# MotorShield.net
KiCad netlist of a schematic drawn in EAGLE
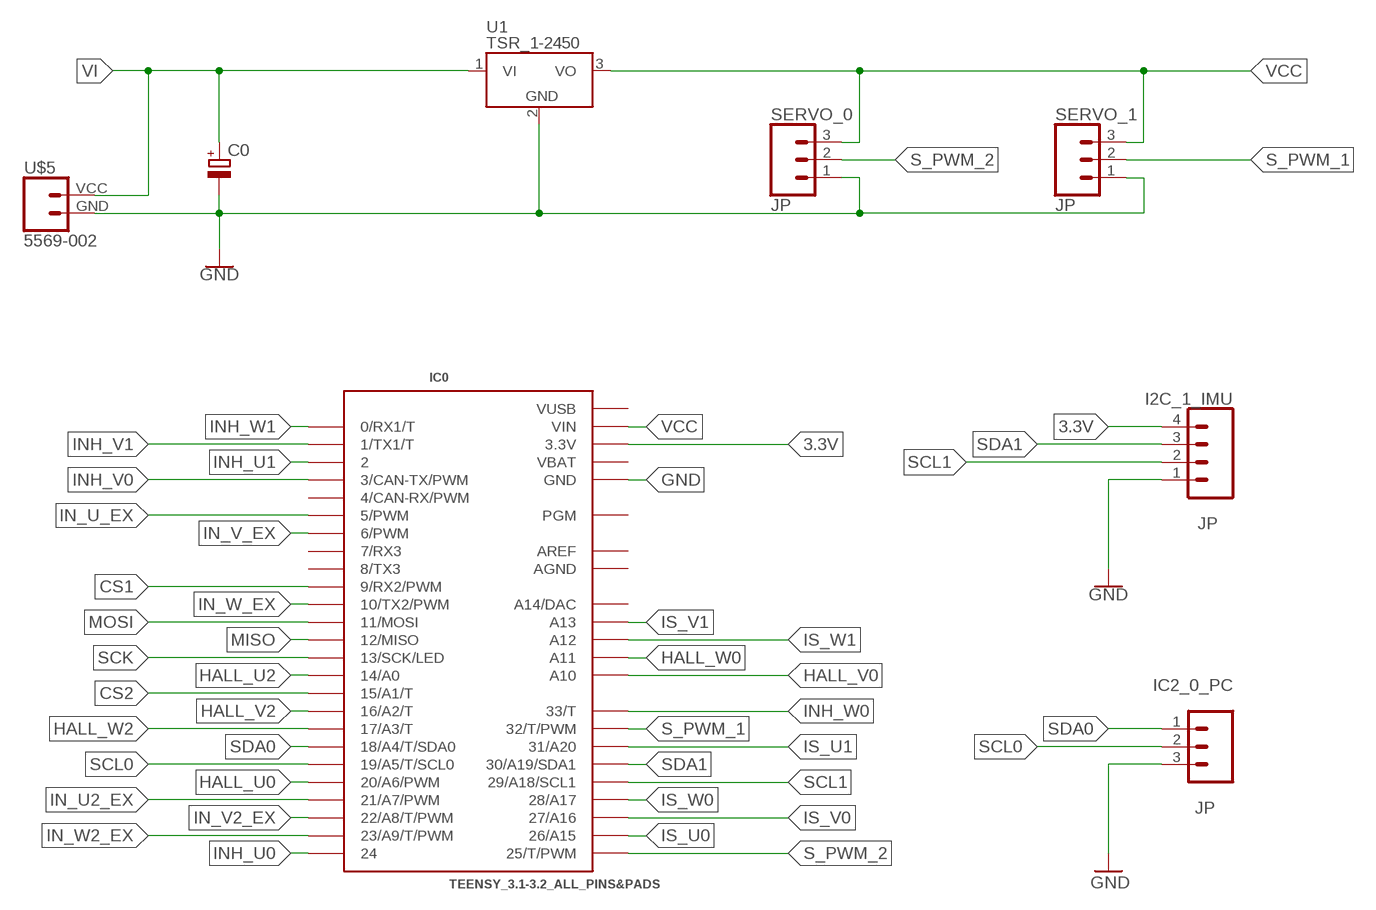
[diagram p0: schematic, sheet 1, part 1 of 2]
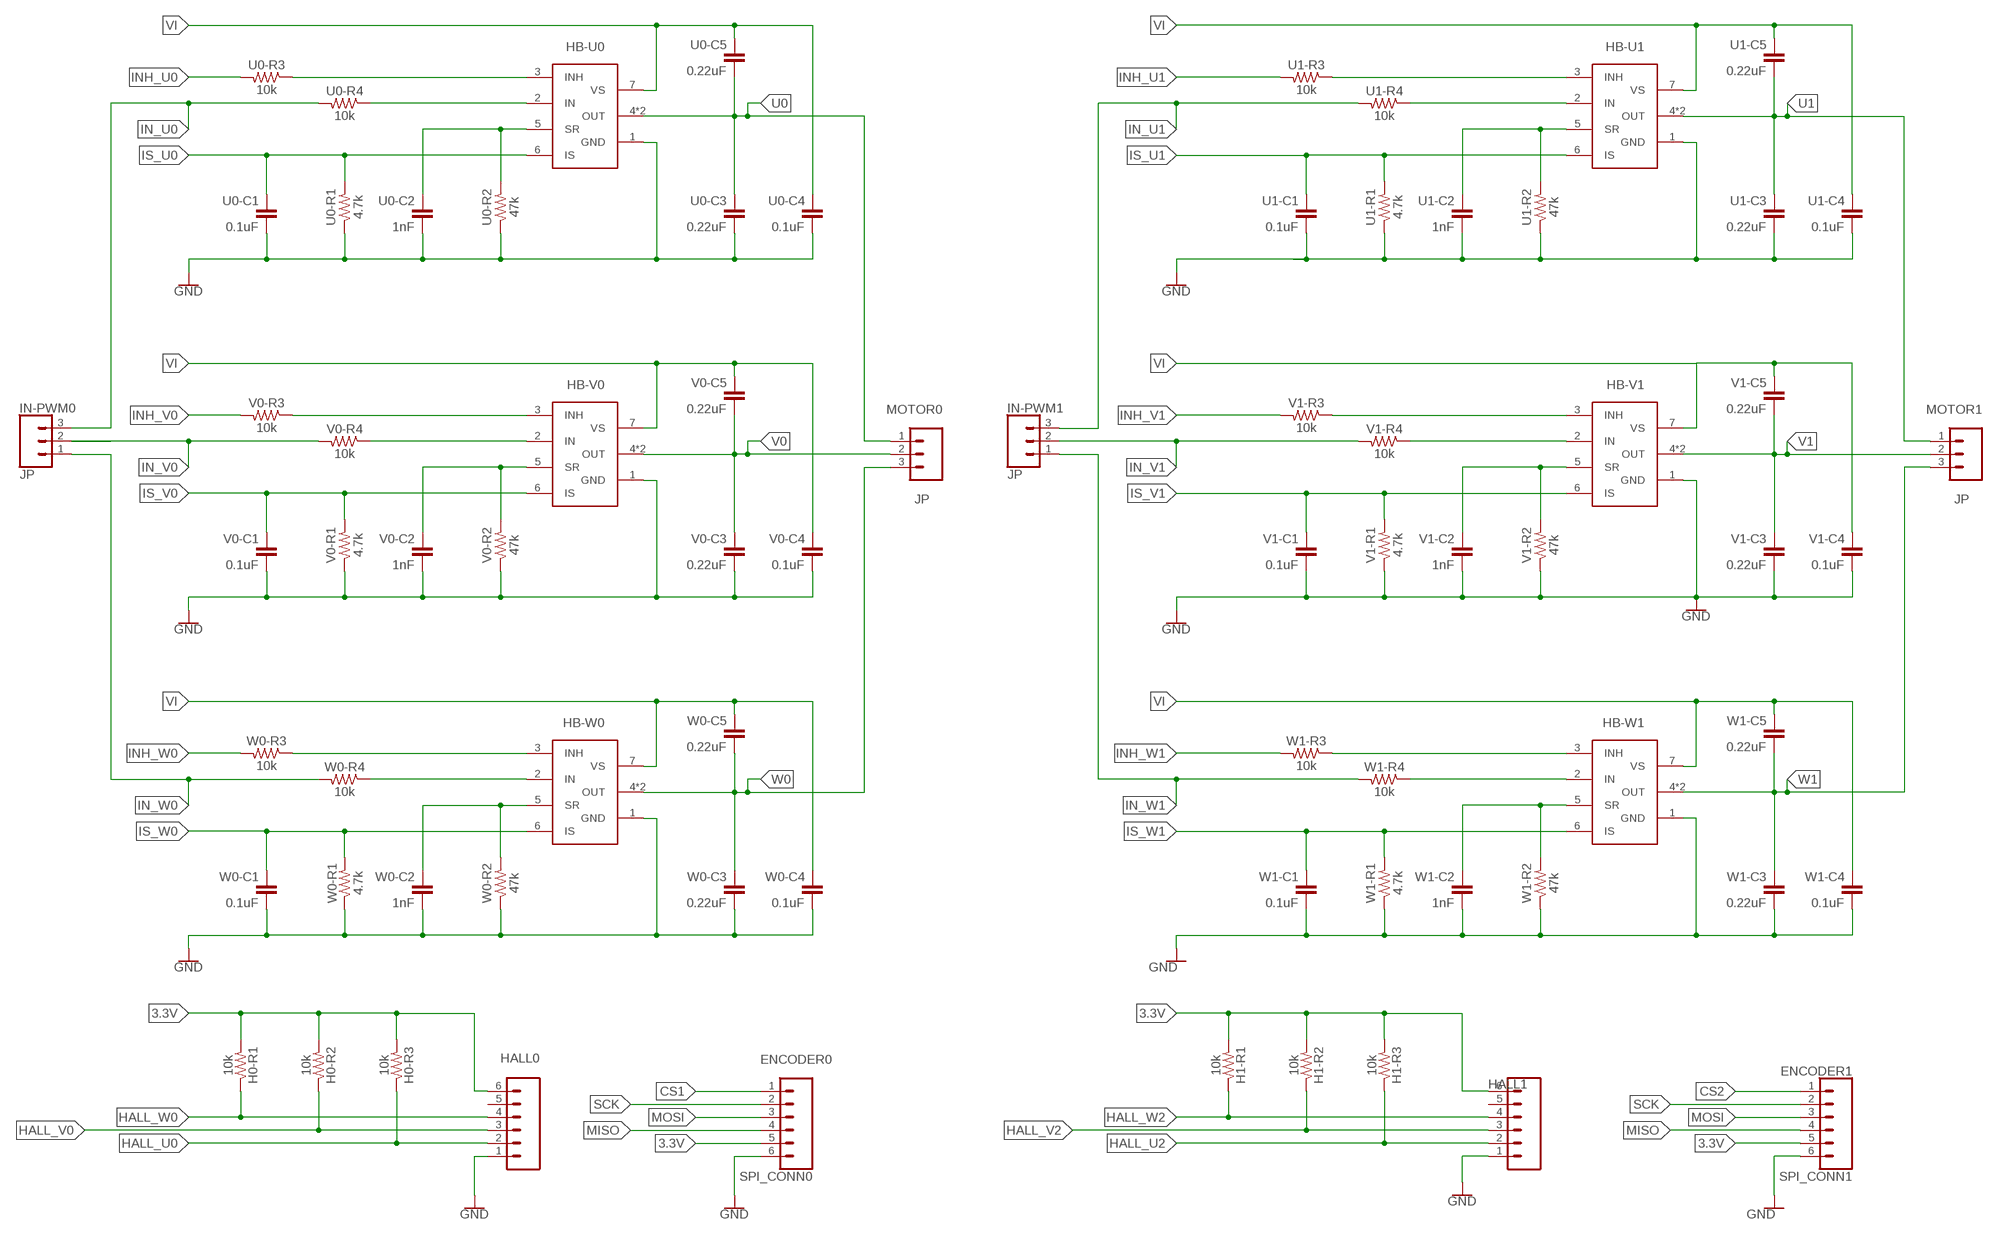
[diagram p1: schematic, sheet 1, part 2 of 2]

(export (version "E")
  (design (tool "Eeschema 10.0.6"))
  (components
    (comp (ref "C0")
      (value "CPOL-EUE2,5-6E")
      (footprint "eagle-import:E2,5-6E")
      (libsource (lib "eagle-import") (part "CPOL-EUE2,5-6E"))
    )
    (comp (ref "H0-R1")
      (value "10k")
      (footprint "eagle-import:0603")
      (libsource (lib "eagle-import") (part "10KOHM-0603-1/10W-1%"))
    )
    (comp (ref "H0-R2")
      (value "10k")
      (footprint "eagle-import:0603")
      (libsource (lib "eagle-import") (part "10KOHM-0603-1/10W-1%"))
    )
    (comp (ref "H0-R3")
      (value "10k")
      (footprint "eagle-import:0603")
      (libsource (lib "eagle-import") (part "10KOHM-0603-1/10W-1%"))
    )
    (comp (ref "H1-R1")
      (value "10k")
      (footprint "eagle-import:0603")
      (libsource (lib "eagle-import") (part "10KOHM-0603-1/10W-1%"))
    )
    (comp (ref "H1-R2")
      (value "10k")
      (footprint "eagle-import:0603")
      (libsource (lib "eagle-import") (part "10KOHM-0603-1/10W-1%"))
    )
    (comp (ref "H1-R3")
      (value "10k")
      (footprint "eagle-import:0603")
      (libsource (lib "eagle-import") (part "10KOHM-0603-1/10W-1%"))
    )
    (comp (ref "HALL0")
      (value "CONN_06SMD-1MM")
      (footprint "eagle-import:1X06-1MM")
      (libsource (lib "eagle-import") (part "CONN_06SMD-1MM"))
    )
    (comp (ref "HALL1")
      (value "CONN_06SMD-1MM")
      (footprint "eagle-import:1X06-1MM")
      (libsource (lib "eagle-import") (part "CONN_06SMD-1MM"))
    )
    (comp (ref "HB-U0")
      (value "IFX007TZZZZ")
      (footprint "eagle-import:P-TO263-7-1")
      (libsource (lib "eagle-import") (part "IFX007TZZZZ"))
    )
    (comp (ref "HB-U1")
      (value "IFX007TZZZZ")
      (footprint "eagle-import:P-TO263-7-1")
      (libsource (lib "eagle-import") (part "IFX007TZZZZ"))
    )
    (comp (ref "HB-V0")
      (value "IFX007TZZZZ")
      (footprint "eagle-import:P-TO263-7-1")
      (libsource (lib "eagle-import") (part "IFX007TZZZZ"))
    )
    (comp (ref "HB-V1")
      (value "IFX007TZZZZ")
      (footprint "eagle-import:P-TO263-7-1")
      (libsource (lib "eagle-import") (part "IFX007TZZZZ"))
    )
    (comp (ref "HB-W0")
      (value "IFX007TZZZZ")
      (footprint "eagle-import:P-TO263-7-1")
      (libsource (lib "eagle-import") (part "IFX007TZZZZ"))
    )
    (comp (ref "HB-W1")
      (value "IFX007TZZZZ")
      (footprint "eagle-import:P-TO263-7-1")
      (libsource (lib "eagle-import") (part "IFX007TZZZZ"))
    )
    (comp (ref "I2C_1_IMU")
      (value "JP")
      (footprint "eagle-import:1X04_NO_SILK")
      (libsource (lib "eagle-import") (part "CONN_041X04_NO_SILK"))
    )
    (comp (ref "IC0")
      (value "TEENSY_3.1-3.2_ALL_PINS&PADS")
      (footprint "eagle-import:TEENSY_3.0-3.2_ALL_PINS_&_PADS")
      (libsource (lib "eagle-import") (part "TEENSY_3.1-3.2_ALL_PINS&PADS"))
    )
    (comp (ref "IC2_0_PC")
      (value "JP")
      (footprint "eagle-import:1X03_NO_SILK")
      (libsource (lib "eagle-import") (part "CONN_031X03_NO_SILK"))
    )
    (comp (ref "IN-PWM0")
      (value "JP")
      (footprint "eagle-import:1X03_NO_SILK")
      (libsource (lib "eagle-import") (part "CONN_031X03_NO_SILK"))
    )
    (comp (ref "IN-PWM1")
      (value "JP")
      (footprint "eagle-import:1X03_NO_SILK")
      (fields (field (name "SPICEPREFIX") "J"))
      (libsource (lib "eagle-import") (part "CONN_031X03_NO_SILK"))
    )
    (comp (ref "MOTOR0")
      (value "JP")
      (footprint "eagle-import:1X03_NO_SILK")
      (libsource (lib "eagle-import") (part "CONN_031X03_NO_SILK"))
    )
    (comp (ref "MOTOR1")
      (value "JP")
      (footprint "eagle-import:1X03_NO_SILK")
      (libsource (lib "eagle-import") (part "CONN_031X03_NO_SILK"))
    )
    (comp (ref "SERVO_0")
      (value "JP")
      (footprint "eagle-import:1X03_NO_SILK")
      (libsource (lib "eagle-import") (part "CONN_031X03_NO_SILK"))
    )
    (comp (ref "SERVO_1")
      (value "JP")
      (footprint "eagle-import:1X03_NO_SILK")
      (libsource (lib "eagle-import") (part "CONN_031X03_NO_SILK"))
    )
    (comp (ref "SPI_CONN0")
      (value "ENCODER0")
      (footprint "eagle-import:1X06-1MM")
      (libsource (lib "eagle-import") (part "CONN_06SMD-1MM"))
    )
    (comp (ref "SPI_CONN1")
      (value "ENCODER1")
      (footprint "eagle-import:1X06-1MM")
      (libsource (lib "eagle-import") (part "CONN_06SMD-1MM"))
    )
    (comp (ref "U$5")
      (value "5569-002")
      (footprint "eagle-import:5569-002")
      (libsource (lib "eagle-import") (part "5569-002"))
    )
    (comp (ref "U0-C1")
      (value "0.1uF")
      (footprint "eagle-import:0603")
      (libsource (lib "eagle-import") (part "0.1UF-0603-25V-5%"))
    )
    (comp (ref "U0-C2")
      (value "1nF")
      (footprint "eagle-import:0603")
      (libsource (lib "eagle-import") (part "1.0NF/1000PF-0603-50V-10%"))
    )
    (comp (ref "U0-C3")
      (value "0.22uF")
      (footprint "eagle-import:0603")
      (libsource (lib "eagle-import") (part "0.22UF-0603-25V-10%"))
    )
    (comp (ref "U0-C4")
      (value "0.1uF")
      (footprint "eagle-import:0603")
      (libsource (lib "eagle-import") (part "0.1UF-0603-25V-5%"))
    )
    (comp (ref "U0-C5")
      (value "0.22uF")
      (footprint "eagle-import:0603")
      (libsource (lib "eagle-import") (part "0.22UF-0603-25V-10%"))
    )
    (comp (ref "U0-R1")
      (value "4.7k")
      (footprint "eagle-import:0603")
      (libsource (lib "eagle-import") (part "4.7KOHM-0603-1/10W-1%"))
    )
    (comp (ref "U0-R2")
      (value "47k")
      (footprint "eagle-import:0603")
      (libsource (lib "eagle-import") (part "47KOHM-0603-1/10W-1%"))
    )
    (comp (ref "U0-R3")
      (value "10k")
      (footprint "eagle-import:0603")
      (libsource (lib "eagle-import") (part "10KOHM-0603-1/10W-1%"))
    )
    (comp (ref "U0-R4")
      (value "10k")
      (footprint "eagle-import:0603")
      (libsource (lib "eagle-import") (part "10KOHM-0603-1/10W-1%"))
    )
    (comp (ref "U1")
      (value "TSR_1-2450")
      (footprint "eagle-import:TSR-1")
      (libsource (lib "eagle-import") (part "TSR_1-2450"))
    )
    (comp (ref "U1-C1")
      (value "0.1uF")
      (footprint "eagle-import:0603")
      (libsource (lib "eagle-import") (part "0.1UF-0603-25V-5%"))
    )
    (comp (ref "U1-C2")
      (value "1nF")
      (footprint "eagle-import:0603")
      (libsource (lib "eagle-import") (part "1.0NF/1000PF-0603-50V-10%"))
    )
    (comp (ref "U1-C3")
      (value "0.22uF")
      (footprint "eagle-import:0603")
      (libsource (lib "eagle-import") (part "0.22UF-0603-25V-10%"))
    )
    (comp (ref "U1-C4")
      (value "0.1uF")
      (footprint "eagle-import:0603")
      (libsource (lib "eagle-import") (part "0.1UF-0603-25V-5%"))
    )
    (comp (ref "U1-C5")
      (value "0.22uF")
      (footprint "eagle-import:0603")
      (libsource (lib "eagle-import") (part "0.22UF-0603-25V-10%"))
    )
    (comp (ref "U1-R1")
      (value "4.7k")
      (footprint "eagle-import:0603")
      (libsource (lib "eagle-import") (part "4.7KOHM-0603-1/10W-1%"))
    )
    (comp (ref "U1-R2")
      (value "47k")
      (footprint "eagle-import:0603")
      (libsource (lib "eagle-import") (part "47KOHM-0603-1/10W-1%"))
    )
    (comp (ref "U1-R3")
      (value "10k")
      (footprint "eagle-import:0603")
      (libsource (lib "eagle-import") (part "10KOHM-0603-1/10W-1%"))
    )
    (comp (ref "U1-R4")
      (value "10k")
      (footprint "eagle-import:0603")
      (libsource (lib "eagle-import") (part "10KOHM-0603-1/10W-1%"))
    )
    (comp (ref "V0-C1")
      (value "0.1uF")
      (footprint "eagle-import:0603")
      (libsource (lib "eagle-import") (part "0.1UF-0603-25V-5%"))
    )
    (comp (ref "V0-C2")
      (value "1nF")
      (footprint "eagle-import:0603")
      (libsource (lib "eagle-import") (part "1.0NF/1000PF-0603-50V-10%"))
    )
    (comp (ref "V0-C3")
      (value "0.22uF")
      (footprint "eagle-import:0603")
      (libsource (lib "eagle-import") (part "0.22UF-0603-25V-10%"))
    )
    (comp (ref "V0-C4")
      (value "0.1uF")
      (footprint "eagle-import:0603")
      (libsource (lib "eagle-import") (part "0.1UF-0603-25V-5%"))
    )
    (comp (ref "V0-C5")
      (value "0.22uF")
      (footprint "eagle-import:0603")
      (libsource (lib "eagle-import") (part "0.22UF-0603-25V-10%"))
    )
    (comp (ref "V0-R1")
      (value "4.7k")
      (footprint "eagle-import:0603")
      (libsource (lib "eagle-import") (part "4.7KOHM-0603-1/10W-1%"))
    )
    (comp (ref "V0-R2")
      (value "47k")
      (footprint "eagle-import:0603")
      (libsource (lib "eagle-import") (part "47KOHM-0603-1/10W-1%"))
    )
    (comp (ref "V0-R3")
      (value "10k")
      (footprint "eagle-import:0603")
      (libsource (lib "eagle-import") (part "10KOHM-0603-1/10W-1%"))
    )
    (comp (ref "V0-R4")
      (value "10k")
      (footprint "eagle-import:0603")
      (libsource (lib "eagle-import") (part "10KOHM-0603-1/10W-1%"))
    )
    (comp (ref "V1-C1")
      (value "0.1uF")
      (footprint "eagle-import:0603")
      (libsource (lib "eagle-import") (part "0.1UF-0603-25V-5%"))
    )
    (comp (ref "V1-C2")
      (value "1nF")
      (footprint "eagle-import:0603")
      (libsource (lib "eagle-import") (part "1.0NF/1000PF-0603-50V-10%"))
    )
    (comp (ref "V1-C3")
      (value "0.22uF")
      (footprint "eagle-import:0603")
      (libsource (lib "eagle-import") (part "0.22UF-0603-25V-10%"))
    )
    (comp (ref "V1-C4")
      (value "0.1uF")
      (footprint "eagle-import:0603")
      (libsource (lib "eagle-import") (part "0.1UF-0603-25V-5%"))
    )
    (comp (ref "V1-C5")
      (value "0.22uF")
      (footprint "eagle-import:0603")
      (libsource (lib "eagle-import") (part "0.22UF-0603-25V-10%"))
    )
    (comp (ref "V1-R1")
      (value "4.7k")
      (footprint "eagle-import:0603")
      (libsource (lib "eagle-import") (part "4.7KOHM-0603-1/10W-1%"))
    )
    (comp (ref "V1-R2")
      (value "47k")
      (footprint "eagle-import:0603")
      (libsource (lib "eagle-import") (part "47KOHM-0603-1/10W-1%"))
    )
    (comp (ref "V1-R3")
      (value "10k")
      (footprint "eagle-import:0603")
      (libsource (lib "eagle-import") (part "10KOHM-0603-1/10W-1%"))
    )
    (comp (ref "V1-R4")
      (value "10k")
      (footprint "eagle-import:0603")
      (libsource (lib "eagle-import") (part "10KOHM-0603-1/10W-1%"))
    )
    (comp (ref "W0-C1")
      (value "0.1uF")
      (footprint "eagle-import:0603")
      (libsource (lib "eagle-import") (part "0.1UF-0603-25V-5%"))
    )
    (comp (ref "W0-C2")
      (value "1nF")
      (footprint "eagle-import:0603")
      (libsource (lib "eagle-import") (part "1.0NF/1000PF-0603-50V-10%"))
    )
    (comp (ref "W0-C3")
      (value "0.22uF")
      (footprint "eagle-import:0603")
      (libsource (lib "eagle-import") (part "0.22UF-0603-25V-10%"))
    )
    (comp (ref "W0-C4")
      (value "0.1uF")
      (footprint "eagle-import:0603")
      (libsource (lib "eagle-import") (part "0.1UF-0603-25V-5%"))
    )
    (comp (ref "W0-C5")
      (value "0.22uF")
      (footprint "eagle-import:0603")
      (libsource (lib "eagle-import") (part "0.22UF-0603-25V-10%"))
    )
    (comp (ref "W0-R1")
      (value "4.7k")
      (footprint "eagle-import:0603")
      (libsource (lib "eagle-import") (part "4.7KOHM-0603-1/10W-1%"))
    )
    (comp (ref "W0-R2")
      (value "47k")
      (footprint "eagle-import:0603")
      (libsource (lib "eagle-import") (part "47KOHM-0603-1/10W-1%"))
    )
    (comp (ref "W0-R3")
      (value "10k")
      (footprint "eagle-import:0603")
      (libsource (lib "eagle-import") (part "10KOHM-0603-1/10W-1%"))
    )
    (comp (ref "W0-R4")
      (value "10k")
      (footprint "eagle-import:0603")
      (libsource (lib "eagle-import") (part "10KOHM-0603-1/10W-1%"))
    )
    (comp (ref "W1-C1")
      (value "0.1uF")
      (footprint "eagle-import:0603")
      (libsource (lib "eagle-import") (part "0.1UF-0603-25V-5%"))
    )
    (comp (ref "W1-C2")
      (value "1nF")
      (footprint "eagle-import:0603")
      (libsource (lib "eagle-import") (part "1.0NF/1000PF-0603-50V-10%"))
    )
    (comp (ref "W1-C3")
      (value "0.22uF")
      (footprint "eagle-import:0603")
      (libsource (lib "eagle-import") (part "0.22UF-0603-25V-10%"))
    )
    (comp (ref "W1-C4")
      (value "0.1uF")
      (footprint "eagle-import:0603")
      (libsource (lib "eagle-import") (part "0.1UF-0603-25V-5%"))
    )
    (comp (ref "W1-C5")
      (value "0.22uF")
      (footprint "eagle-import:0603")
      (libsource (lib "eagle-import") (part "0.22UF-0603-25V-10%"))
    )
    (comp (ref "W1-R1")
      (value "4.7k")
      (footprint "eagle-import:0603")
      (libsource (lib "eagle-import") (part "4.7KOHM-0603-1/10W-1%"))
    )
    (comp (ref "W1-R2")
      (value "47k")
      (footprint "eagle-import:0603")
      (libsource (lib "eagle-import") (part "47KOHM-0603-1/10W-1%"))
    )
    (comp (ref "W1-R3")
      (value "10k")
      (footprint "eagle-import:0603")
      (libsource (lib "eagle-import") (part "10KOHM-0603-1/10W-1%"))
    )
    (comp (ref "W1-R4")
      (value "10k")
      (footprint "eagle-import:0603")
      (libsource (lib "eagle-import") (part "10KOHM-0603-1/10W-1%"))
    )
  )
  (nets
    (net (code "1") (name "/AGND") (class "Default")
      (node (ref "IC0") (pin "AGND") (pinfunction "AGND_AGND") (pintype "power_in"))
    )
    (net (code "2") (name "/AREF") (class "Default")
      (node (ref "IC0") (pin "AREF") (pinfunction "AREF_AREF") (pintype "power_in"))
    )
    (net (code "3") (name "/VBAT") (class "Default")
      (node (ref "IC0") (pin "VBAT") (pinfunction "VBAT_VBAT") (pintype "power_in"))
    )
    (net (code "4") (name "/VUSB") (class "Default")
      (node (ref "IC0") (pin "VUSB") (pinfunction "VUSB_VUSB") (pintype "power_in"))
    )
    (net (code "5") (name "3.3V") (class "Default")
      (node (ref "H0-R1") (pin "2") (pinfunction "2_2") (pintype "passive"))
      (node (ref "H0-R2") (pin "2") (pinfunction "2_2") (pintype "passive"))
      (node (ref "H0-R3") (pin "2") (pinfunction "2_2") (pintype "passive"))
      (node (ref "H1-R1") (pin "2") (pinfunction "2_2") (pintype "passive"))
      (node (ref "H1-R2") (pin "2") (pinfunction "2_2") (pintype "passive"))
      (node (ref "H1-R3") (pin "2") (pinfunction "2_2") (pintype "passive"))
      (node (ref "HALL0") (pin "6") (pinfunction "6_6") (pintype "passive"))
      (node (ref "HALL1") (pin "6") (pinfunction "6_6") (pintype "passive"))
      (node (ref "I2C_1_IMU") (pin "4") (pinfunction "4_4") (pintype "passive"))
      (node (ref "IC0") (pin "3.3V") (pinfunction "3.3V_3.3V") (pintype "power_in"))
      (node (ref "IC0") (pin "3.3V1") (pinfunction "3.3V_3.3V1") (pintype "power_in"))
      (node (ref "IC0") (pin "3.3V2") (pinfunction "3.3V_3.3V2") (pintype "power_in"))
      (node (ref "SPI_CONN0") (pin "5") (pinfunction "5_5") (pintype "passive"))
      (node (ref "SPI_CONN1") (pin "5") (pinfunction "5_5") (pintype "passive"))
    )
    (net (code "6") (name "CS1") (class "Default")
      (node (ref "IC0") (pin "9") (pinfunction "9/RX2/PWM_9") (pintype "bidirectional"))
      (node (ref "SPI_CONN0") (pin "1") (pinfunction "1_1") (pintype "passive"))
    )
    (net (code "7") (name "CS2") (class "Default")
      (node (ref "IC0") (pin "15/A1") (pinfunction "15/A1/T_15/A1") (pintype "bidirectional"))
      (node (ref "SPI_CONN1") (pin "1") (pinfunction "1_1") (pintype "passive"))
    )
    (net (code "8") (name "GND") (class "Default")
      (node (ref "C0") (pin "-") (pinfunction "-_-") (pintype "passive"))
      (node (ref "HALL0") (pin "1") (pinfunction "1_1") (pintype "passive"))
      (node (ref "HALL1") (pin "1") (pinfunction "1_1") (pintype "passive"))
      (node (ref "HB-U0") (pin "1") (pinfunction "GND_1") (pintype "power_in"))
      (node (ref "HB-U1") (pin "1") (pinfunction "GND_1") (pintype "power_in"))
      (node (ref "HB-V0") (pin "1") (pinfunction "GND_1") (pintype "power_in"))
      (node (ref "HB-V1") (pin "1") (pinfunction "GND_1") (pintype "power_in"))
      (node (ref "HB-W0") (pin "1") (pinfunction "GND_1") (pintype "power_in"))
      (node (ref "HB-W1") (pin "1") (pinfunction "GND_1") (pintype "power_in"))
      (node (ref "I2C_1_IMU") (pin "1") (pinfunction "1_1") (pintype "passive"))
      (node (ref "IC0") (pin "GND") (pinfunction "GND_GND") (pintype "power_in"))
      (node (ref "IC0") (pin "GND1") (pinfunction "GND_GND1") (pintype "power_in"))
      (node (ref "IC0") (pin "GND2") (pinfunction "GND_GND2") (pintype "power_in"))
      (node (ref "IC2_0_PC") (pin "3") (pinfunction "3_3") (pintype "passive"))
      (node (ref "SERVO_0") (pin "1") (pinfunction "1_1") (pintype "passive"))
      (node (ref "SERVO_1") (pin "1") (pinfunction "1_1") (pintype "passive"))
      (node (ref "SPI_CONN0") (pin "6") (pinfunction "6_6") (pintype "passive"))
      (node (ref "SPI_CONN1") (pin "6") (pinfunction "6_6") (pintype "passive"))
      (node (ref "U$5") (pin "GND") (pinfunction "1_GND") (pintype "passive"))
      (node (ref "U0-C1") (pin "2") (pinfunction "2_2") (pintype "passive"))
      (node (ref "U0-C2") (pin "1") (pinfunction "1_1") (pintype "passive"))
      (node (ref "U0-C3") (pin "1") (pinfunction "1_1") (pintype "passive"))
      (node (ref "U0-C4") (pin "2") (pinfunction "2_2") (pintype "passive"))
      (node (ref "U0-R1") (pin "1") (pinfunction "1_1") (pintype "passive"))
      (node (ref "U0-R2") (pin "1") (pinfunction "1_1") (pintype "passive"))
      (node (ref "U1") (pin "2") (pinfunction "GND_2") (pintype "power_in"))
      (node (ref "U1-C1") (pin "2") (pinfunction "2_2") (pintype "passive"))
      (node (ref "U1-C2") (pin "1") (pinfunction "1_1") (pintype "passive"))
      (node (ref "U1-C3") (pin "1") (pinfunction "1_1") (pintype "passive"))
      (node (ref "U1-C4") (pin "2") (pinfunction "2_2") (pintype "passive"))
      (node (ref "U1-R1") (pin "1") (pinfunction "1_1") (pintype "passive"))
      (node (ref "U1-R2") (pin "1") (pinfunction "1_1") (pintype "passive"))
      (node (ref "V0-C1") (pin "2") (pinfunction "2_2") (pintype "passive"))
      (node (ref "V0-C2") (pin "1") (pinfunction "1_1") (pintype "passive"))
      (node (ref "V0-C3") (pin "1") (pinfunction "1_1") (pintype "passive"))
      (node (ref "V0-C4") (pin "2") (pinfunction "2_2") (pintype "passive"))
      (node (ref "V0-R1") (pin "1") (pinfunction "1_1") (pintype "passive"))
      (node (ref "V0-R2") (pin "1") (pinfunction "1_1") (pintype "passive"))
      (node (ref "V1-C1") (pin "2") (pinfunction "2_2") (pintype "passive"))
      (node (ref "V1-C2") (pin "1") (pinfunction "1_1") (pintype "passive"))
      (node (ref "V1-C3") (pin "1") (pinfunction "1_1") (pintype "passive"))
      (node (ref "V1-C4") (pin "2") (pinfunction "2_2") (pintype "passive"))
      (node (ref "V1-R1") (pin "1") (pinfunction "1_1") (pintype "passive"))
      (node (ref "V1-R2") (pin "1") (pinfunction "1_1") (pintype "passive"))
      (node (ref "W0-C1") (pin "2") (pinfunction "2_2") (pintype "passive"))
      (node (ref "W0-C2") (pin "1") (pinfunction "1_1") (pintype "passive"))
      (node (ref "W0-C3") (pin "1") (pinfunction "1_1") (pintype "passive"))
      (node (ref "W0-C4") (pin "2") (pinfunction "2_2") (pintype "passive"))
      (node (ref "W0-R1") (pin "1") (pinfunction "1_1") (pintype "passive"))
      (node (ref "W0-R2") (pin "1") (pinfunction "1_1") (pintype "passive"))
      (node (ref "W1-C1") (pin "2") (pinfunction "2_2") (pintype "passive"))
      (node (ref "W1-C2") (pin "1") (pinfunction "1_1") (pintype "passive"))
      (node (ref "W1-C3") (pin "1") (pinfunction "1_1") (pintype "passive"))
      (node (ref "W1-C4") (pin "2") (pinfunction "2_2") (pintype "passive"))
      (node (ref "W1-R1") (pin "1") (pinfunction "1_1") (pintype "passive"))
      (node (ref "W1-R2") (pin "1") (pinfunction "1_1") (pintype "passive"))
    )
    (net (code "9") (name "HALL_U0") (class "Default")
      (node (ref "H0-R3") (pin "1") (pinfunction "1_1") (pintype "passive"))
      (node (ref "HALL0") (pin "2") (pinfunction "2_2") (pintype "passive"))
      (node (ref "IC0") (pin "20/A6") (pinfunction "20/A6/PWM_20/A6") (pintype "bidirectional"))
    )
    (net (code "10") (name "HALL_U2") (class "Default")
      (node (ref "H1-R3") (pin "1") (pinfunction "1_1") (pintype "passive"))
      (node (ref "HALL1") (pin "2") (pinfunction "2_2") (pintype "passive"))
      (node (ref "IC0") (pin "14/A0") (pinfunction "14/A0_14/A0") (pintype "bidirectional"))
    )
    (net (code "11") (name "HALL_V0") (class "Default")
      (node (ref "H0-R2") (pin "1") (pinfunction "1_1") (pintype "passive"))
      (node (ref "HALL0") (pin "3") (pinfunction "3_3") (pintype "passive"))
      (node (ref "IC0") (pin "A10") (pinfunction "A10_A10") (pintype "bidirectional"))
    )
    (net (code "12") (name "HALL_V2") (class "Default")
      (node (ref "H1-R2") (pin "1") (pinfunction "1_1") (pintype "passive"))
      (node (ref "HALL1") (pin "3") (pinfunction "3_3") (pintype "passive"))
      (node (ref "IC0") (pin "16/A2") (pinfunction "16/A2/T_16/A2") (pintype "bidirectional"))
    )
    (net (code "13") (name "HALL_W0") (class "Default")
      (node (ref "H0-R1") (pin "1") (pinfunction "1_1") (pintype "passive"))
      (node (ref "HALL0") (pin "4") (pinfunction "4_4") (pintype "passive"))
      (node (ref "IC0") (pin "A11") (pinfunction "A11_A11") (pintype "bidirectional"))
    )
    (net (code "14") (name "HALL_W2") (class "Default")
      (node (ref "H1-R1") (pin "1") (pinfunction "1_1") (pintype "passive"))
      (node (ref "HALL1") (pin "4") (pinfunction "4_4") (pintype "passive"))
      (node (ref "IC0") (pin "17/A3") (pinfunction "17/A3/T_17/A3") (pintype "bidirectional"))
    )
    (net (code "15") (name "INH_U0") (class "Default")
      (node (ref "IC0") (pin "24") (pinfunction "24_24") (pintype "bidirectional"))
      (node (ref "U0-R3") (pin "2") (pinfunction "2_2") (pintype "passive"))
    )
    (net (code "16") (name "INH_U1") (class "Default")
      (node (ref "IC0") (pin "2") (pinfunction "2_2") (pintype "bidirectional"))
      (node (ref "U1-R3") (pin "2") (pinfunction "2_2") (pintype "passive"))
    )
    (net (code "17") (name "INH_V0") (class "Default")
      (node (ref "IC0") (pin "3") (pinfunction "3/CAN-TX/PWM_3") (pintype "bidirectional"))
      (node (ref "V0-R3") (pin "2") (pinfunction "2_2") (pintype "passive"))
    )
    (net (code "18") (name "INH_V1") (class "Default")
      (node (ref "IC0") (pin "1") (pinfunction "1/TX1/T_1") (pintype "bidirectional"))
      (node (ref "V1-R3") (pin "2") (pinfunction "2_2") (pintype "passive"))
    )
    (net (code "19") (name "INH_W0") (class "Default")
      (node (ref "IC0") (pin "33") (pinfunction "33/T_33") (pintype "bidirectional"))
      (node (ref "W0-R3") (pin "2") (pinfunction "2_2") (pintype "passive"))
    )
    (net (code "20") (name "INH_W1") (class "Default")
      (node (ref "IC0") (pin "0") (pinfunction "0/RX1/T_0") (pintype "bidirectional"))
      (node (ref "W1-R3") (pin "2") (pinfunction "2_2") (pintype "passive"))
    )
    (net (code "21") (name "IN_U0") (class "Default")
      (node (ref "IN-PWM0") (pin "3") (pinfunction "3_3") (pintype "passive"))
      (node (ref "U0-R4") (pin "2") (pinfunction "2_2") (pintype "passive"))
    )
    (net (code "22") (name "IN_U1") (class "Default")
      (node (ref "IN-PWM1") (pin "3") (pinfunction "3_3") (pintype "passive"))
      (node (ref "U1-R4") (pin "2") (pinfunction "2_2") (pintype "passive"))
    )
    (net (code "23") (name "IN_U2_EX") (class "Default")
      (node (ref "IC0") (pin "21/A7") (pinfunction "21/A7/PWM_21/A7") (pintype "bidirectional"))
    )
    (net (code "24") (name "IN_U_EX") (class "Default")
      (node (ref "IC0") (pin "5") (pinfunction "5/PWM_5") (pintype "bidirectional"))
    )
    (net (code "25") (name "IN_V0") (class "Default")
      (node (ref "IN-PWM0") (pin "2") (pinfunction "2_2") (pintype "passive"))
      (node (ref "V0-R4") (pin "2") (pinfunction "2_2") (pintype "passive"))
    )
    (net (code "26") (name "IN_V1") (class "Default")
      (node (ref "IN-PWM1") (pin "2") (pinfunction "2_2") (pintype "passive"))
      (node (ref "V1-R4") (pin "2") (pinfunction "2_2") (pintype "passive"))
    )
    (net (code "27") (name "IN_V2_EX") (class "Default")
      (node (ref "IC0") (pin "22/A8") (pinfunction "22/A8/T/PWM_22/A8") (pintype "bidirectional"))
    )
    (net (code "28") (name "IN_V_EX") (class "Default")
      (node (ref "IC0") (pin "6") (pinfunction "6/PWM_6") (pintype "bidirectional"))
    )
    (net (code "29") (name "IN_W0") (class "Default")
      (node (ref "IN-PWM0") (pin "1") (pinfunction "1_1") (pintype "passive"))
      (node (ref "W0-R4") (pin "2") (pinfunction "2_2") (pintype "passive"))
    )
    (net (code "30") (name "IN_W1") (class "Default")
      (node (ref "IN-PWM1") (pin "1") (pinfunction "1_1") (pintype "passive"))
      (node (ref "W1-R4") (pin "2") (pinfunction "2_2") (pintype "passive"))
    )
    (net (code "31") (name "IN_W2_EX") (class "Default")
      (node (ref "IC0") (pin "23/A9") (pinfunction "23/A9/T/PWM_23/A9") (pintype "bidirectional"))
    )
    (net (code "32") (name "IN_W_EX") (class "Default")
      (node (ref "IC0") (pin "10") (pinfunction "10/TX2/PWM_10") (pintype "bidirectional"))
    )
    (net (code "33") (name "IS_U0") (class "Default")
      (node (ref "HB-U0") (pin "6") (pinfunction "IS_6") (pintype "output"))
      (node (ref "IC0") (pin "26") (pinfunction "26/A15_26") (pintype "bidirectional"))
      (node (ref "U0-C1") (pin "1") (pinfunction "1_1") (pintype "passive"))
      (node (ref "U0-R1") (pin "2") (pinfunction "2_2") (pintype "passive"))
    )
    (net (code "34") (name "IS_U1") (class "Default")
      (node (ref "HB-U1") (pin "6") (pinfunction "IS_6") (pintype "output"))
      (node (ref "IC0") (pin "31") (pinfunction "31/A20_31") (pintype "bidirectional"))
      (node (ref "U1-C1") (pin "1") (pinfunction "1_1") (pintype "passive"))
      (node (ref "U1-R1") (pin "2") (pinfunction "2_2") (pintype "passive"))
    )
    (net (code "35") (name "IS_V0") (class "Default")
      (node (ref "HB-V0") (pin "6") (pinfunction "IS_6") (pintype "output"))
      (node (ref "IC0") (pin "27") (pinfunction "27/A16_27") (pintype "bidirectional"))
      (node (ref "V0-C1") (pin "1") (pinfunction "1_1") (pintype "passive"))
      (node (ref "V0-R1") (pin "2") (pinfunction "2_2") (pintype "passive"))
    )
    (net (code "36") (name "IS_V1") (class "Default")
      (node (ref "HB-V1") (pin "6") (pinfunction "IS_6") (pintype "output"))
      (node (ref "IC0") (pin "A13") (pinfunction "A13_A13") (pintype "bidirectional"))
      (node (ref "V1-C1") (pin "1") (pinfunction "1_1") (pintype "passive"))
      (node (ref "V1-R1") (pin "2") (pinfunction "2_2") (pintype "passive"))
    )
    (net (code "37") (name "IS_W0") (class "Default")
      (node (ref "HB-W0") (pin "6") (pinfunction "IS_6") (pintype "output"))
      (node (ref "IC0") (pin "28") (pinfunction "28/A17_28") (pintype "bidirectional"))
      (node (ref "W0-C1") (pin "1") (pinfunction "1_1") (pintype "passive"))
      (node (ref "W0-R1") (pin "2") (pinfunction "2_2") (pintype "passive"))
    )
    (net (code "38") (name "IS_W1") (class "Default")
      (node (ref "HB-W1") (pin "6") (pinfunction "IS_6") (pintype "output"))
      (node (ref "IC0") (pin "A12") (pinfunction "A12_A12") (pintype "bidirectional"))
      (node (ref "W1-C1") (pin "1") (pinfunction "1_1") (pintype "passive"))
      (node (ref "W1-R1") (pin "2") (pinfunction "2_2") (pintype "passive"))
    )
    (net (code "39") (name "MISO") (class "Default")
      (node (ref "IC0") (pin "12") (pinfunction "12/MISO_12") (pintype "bidirectional"))
      (node (ref "SPI_CONN0") (pin "4") (pinfunction "4_4") (pintype "passive"))
      (node (ref "SPI_CONN1") (pin "4") (pinfunction "4_4") (pintype "passive"))
    )
    (net (code "40") (name "MOSI") (class "Default")
      (node (ref "IC0") (pin "11") (pinfunction "11/MOSI_11") (pintype "bidirectional"))
      (node (ref "SPI_CONN0") (pin "3") (pinfunction "3_3") (pintype "passive"))
      (node (ref "SPI_CONN1") (pin "3") (pinfunction "3_3") (pintype "passive"))
    )
    (net (code "41") (name "Net-(HB-U0-IN)") (class "Default")
      (node (ref "HB-U0") (pin "2") (pinfunction "IN_2") (pintype "input"))
      (node (ref "U0-R4") (pin "1") (pinfunction "1_1") (pintype "passive"))
    )
    (net (code "42") (name "Net-(HB-U0-INH)") (class "Default")
      (node (ref "HB-U0") (pin "3") (pinfunction "INH_3") (pintype "bidirectional"))
      (node (ref "U0-R3") (pin "1") (pinfunction "1_1") (pintype "passive"))
    )
    (net (code "43") (name "Net-(HB-U0-SR)") (class "Default")
      (node (ref "HB-U0") (pin "5") (pinfunction "SR_5") (pintype "input"))
      (node (ref "U0-C2") (pin "2") (pinfunction "2_2") (pintype "passive"))
      (node (ref "U0-R2") (pin "2") (pinfunction "2_2") (pintype "passive"))
    )
    (net (code "44") (name "Net-(HB-U1-IN)") (class "Default")
      (node (ref "HB-U1") (pin "2") (pinfunction "IN_2") (pintype "input"))
      (node (ref "U1-R4") (pin "1") (pinfunction "1_1") (pintype "passive"))
    )
    (net (code "45") (name "Net-(HB-U1-INH)") (class "Default")
      (node (ref "HB-U1") (pin "3") (pinfunction "INH_3") (pintype "bidirectional"))
      (node (ref "U1-R3") (pin "1") (pinfunction "1_1") (pintype "passive"))
    )
    (net (code "46") (name "Net-(HB-U1-SR)") (class "Default")
      (node (ref "HB-U1") (pin "5") (pinfunction "SR_5") (pintype "input"))
      (node (ref "U1-C2") (pin "2") (pinfunction "2_2") (pintype "passive"))
      (node (ref "U1-R2") (pin "2") (pinfunction "2_2") (pintype "passive"))
    )
    (net (code "47") (name "Net-(HB-V0-IN)") (class "Default")
      (node (ref "HB-V0") (pin "2") (pinfunction "IN_2") (pintype "input"))
      (node (ref "V0-R4") (pin "1") (pinfunction "1_1") (pintype "passive"))
    )
    (net (code "48") (name "Net-(HB-V0-INH)") (class "Default")
      (node (ref "HB-V0") (pin "3") (pinfunction "INH_3") (pintype "bidirectional"))
      (node (ref "V0-R3") (pin "1") (pinfunction "1_1") (pintype "passive"))
    )
    (net (code "49") (name "Net-(HB-V0-SR)") (class "Default")
      (node (ref "HB-V0") (pin "5") (pinfunction "SR_5") (pintype "input"))
      (node (ref "V0-C2") (pin "2") (pinfunction "2_2") (pintype "passive"))
      (node (ref "V0-R2") (pin "2") (pinfunction "2_2") (pintype "passive"))
    )
    (net (code "50") (name "Net-(HB-V1-IN)") (class "Default")
      (node (ref "HB-V1") (pin "2") (pinfunction "IN_2") (pintype "input"))
      (node (ref "V1-R4") (pin "1") (pinfunction "1_1") (pintype "passive"))
    )
    (net (code "51") (name "Net-(HB-V1-INH)") (class "Default")
      (node (ref "HB-V1") (pin "3") (pinfunction "INH_3") (pintype "bidirectional"))
      (node (ref "V1-R3") (pin "1") (pinfunction "1_1") (pintype "passive"))
    )
    (net (code "52") (name "Net-(HB-V1-SR)") (class "Default")
      (node (ref "HB-V1") (pin "5") (pinfunction "SR_5") (pintype "input"))
      (node (ref "V1-C2") (pin "2") (pinfunction "2_2") (pintype "passive"))
      (node (ref "V1-R2") (pin "2") (pinfunction "2_2") (pintype "passive"))
    )
    (net (code "53") (name "Net-(HB-W0-IN)") (class "Default")
      (node (ref "HB-W0") (pin "2") (pinfunction "IN_2") (pintype "input"))
      (node (ref "W0-R4") (pin "1") (pinfunction "1_1") (pintype "passive"))
    )
    (net (code "54") (name "Net-(HB-W0-INH)") (class "Default")
      (node (ref "HB-W0") (pin "3") (pinfunction "INH_3") (pintype "bidirectional"))
      (node (ref "W0-R3") (pin "1") (pinfunction "1_1") (pintype "passive"))
    )
    (net (code "55") (name "Net-(HB-W0-SR)") (class "Default")
      (node (ref "HB-W0") (pin "5") (pinfunction "SR_5") (pintype "input"))
      (node (ref "W0-C2") (pin "2") (pinfunction "2_2") (pintype "passive"))
      (node (ref "W0-R2") (pin "2") (pinfunction "2_2") (pintype "passive"))
    )
    (net (code "56") (name "Net-(HB-W1-IN)") (class "Default")
      (node (ref "HB-W1") (pin "2") (pinfunction "IN_2") (pintype "input"))
      (node (ref "W1-R4") (pin "1") (pinfunction "1_1") (pintype "passive"))
    )
    (net (code "57") (name "Net-(HB-W1-INH)") (class "Default")
      (node (ref "HB-W1") (pin "3") (pinfunction "INH_3") (pintype "bidirectional"))
      (node (ref "W1-R3") (pin "1") (pinfunction "1_1") (pintype "passive"))
    )
    (net (code "58") (name "Net-(HB-W1-SR)") (class "Default")
      (node (ref "HB-W1") (pin "5") (pinfunction "SR_5") (pintype "input"))
      (node (ref "W1-C2") (pin "2") (pinfunction "2_2") (pintype "passive"))
      (node (ref "W1-R2") (pin "2") (pinfunction "2_2") (pintype "passive"))
    )
    (net (code "59") (name "SCK") (class "Default")
      (node (ref "IC0") (pin "13") (pinfunction "13/SCK/LED_13") (pintype "bidirectional"))
      (node (ref "SPI_CONN0") (pin "2") (pinfunction "2_2") (pintype "passive"))
      (node (ref "SPI_CONN1") (pin "2") (pinfunction "2_2") (pintype "passive"))
    )
    (net (code "60") (name "SCL0") (class "Default")
      (node (ref "IC0") (pin "19/A5") (pinfunction "19/A5/T/SCL0_19/A5") (pintype "bidirectional"))
      (node (ref "IC2_0_PC") (pin "2") (pinfunction "2_2") (pintype "passive"))
    )
    (net (code "61") (name "SCL1") (class "Default")
      (node (ref "I2C_1_IMU") (pin "2") (pinfunction "2_2") (pintype "passive"))
      (node (ref "IC0") (pin "29") (pinfunction "29/A18/SCL1_29") (pintype "bidirectional"))
    )
    (net (code "62") (name "SDA0") (class "Default")
      (node (ref "IC0") (pin "18/A4") (pinfunction "18/A4/T/SDA0_18/A4") (pintype "bidirectional"))
      (node (ref "IC2_0_PC") (pin "1") (pinfunction "1_1") (pintype "passive"))
    )
    (net (code "63") (name "SDA1") (class "Default")
      (node (ref "I2C_1_IMU") (pin "3") (pinfunction "3_3") (pintype "passive"))
      (node (ref "IC0") (pin "30") (pinfunction "30/A19/SDA1_30") (pintype "bidirectional"))
    )
    (net (code "64") (name "S_PWM_1") (class "Default")
      (node (ref "IC0") (pin "32") (pinfunction "32/T/PWM_32") (pintype "bidirectional"))
      (node (ref "SERVO_1") (pin "2") (pinfunction "2_2") (pintype "passive"))
    )
    (net (code "65") (name "S_PWM_2") (class "Default")
      (node (ref "IC0") (pin "25") (pinfunction "25/T/PWM_25") (pintype "bidirectional"))
      (node (ref "SERVO_0") (pin "2") (pinfunction "2_2") (pintype "passive"))
    )
    (net (code "66") (name "U0") (class "Default")
      (node (ref "HB-U0") (pin "4") (pinfunction "OUT_4") (pintype "power_in"))
      (node (ref "HB-U0") (pin "8") (pinfunction "OUT_8") (pintype "power_in"))
      (node (ref "MOTOR0") (pin "1") (pinfunction "1_1") (pintype "passive"))
      (node (ref "U0-C3") (pin "2") (pinfunction "2_2") (pintype "passive"))
      (node (ref "U0-C5") (pin "2") (pinfunction "2_2") (pintype "passive"))
    )
    (net (code "67") (name "U1") (class "Default")
      (node (ref "HB-U1") (pin "4") (pinfunction "OUT_4") (pintype "power_in"))
      (node (ref "HB-U1") (pin "8") (pinfunction "OUT_8") (pintype "power_in"))
      (node (ref "MOTOR1") (pin "1") (pinfunction "1_1") (pintype "passive"))
      (node (ref "U1-C3") (pin "2") (pinfunction "2_2") (pintype "passive"))
      (node (ref "U1-C5") (pin "2") (pinfunction "2_2") (pintype "passive"))
    )
    (net (code "68") (name "V0") (class "Default")
      (node (ref "HB-V0") (pin "4") (pinfunction "OUT_4") (pintype "power_in"))
      (node (ref "HB-V0") (pin "8") (pinfunction "OUT_8") (pintype "power_in"))
      (node (ref "MOTOR0") (pin "2") (pinfunction "2_2") (pintype "passive"))
      (node (ref "V0-C3") (pin "2") (pinfunction "2_2") (pintype "passive"))
      (node (ref "V0-C5") (pin "2") (pinfunction "2_2") (pintype "passive"))
    )
    (net (code "69") (name "V1") (class "Default")
      (node (ref "HB-V1") (pin "4") (pinfunction "OUT_4") (pintype "power_in"))
      (node (ref "HB-V1") (pin "8") (pinfunction "OUT_8") (pintype "power_in"))
      (node (ref "MOTOR1") (pin "2") (pinfunction "2_2") (pintype "passive"))
      (node (ref "V1-C3") (pin "2") (pinfunction "2_2") (pintype "passive"))
      (node (ref "V1-C5") (pin "2") (pinfunction "2_2") (pintype "passive"))
    )
    (net (code "70") (name "VCC") (class "Default")
      (node (ref "IC0") (pin "VIN") (pinfunction "VIN_VIN") (pintype "power_in"))
      (node (ref "SERVO_0") (pin "3") (pinfunction "3_3") (pintype "passive"))
      (node (ref "SERVO_1") (pin "3") (pinfunction "3_3") (pintype "passive"))
      (node (ref "U1") (pin "3") (pinfunction "VO_3") (pintype "power_in"))
    )
    (net (code "71") (name "VI") (class "Default")
      (node (ref "C0") (pin "+") (pinfunction "+_+") (pintype "passive"))
      (node (ref "HB-U0") (pin "7") (pinfunction "VS_7") (pintype "power_in"))
      (node (ref "HB-U1") (pin "7") (pinfunction "VS_7") (pintype "power_in"))
      (node (ref "HB-V0") (pin "7") (pinfunction "VS_7") (pintype "power_in"))
      (node (ref "HB-V1") (pin "7") (pinfunction "VS_7") (pintype "power_in"))
      (node (ref "HB-W0") (pin "7") (pinfunction "VS_7") (pintype "power_in"))
      (node (ref "HB-W1") (pin "7") (pinfunction "VS_7") (pintype "power_in"))
      (node (ref "U$5") (pin "VCC") (pinfunction "2_VCC") (pintype "passive"))
      (node (ref "U0-C4") (pin "1") (pinfunction "1_1") (pintype "passive"))
      (node (ref "U0-C5") (pin "1") (pinfunction "1_1") (pintype "passive"))
      (node (ref "U1") (pin "1") (pinfunction "VI_1") (pintype "power_in"))
      (node (ref "U1-C4") (pin "1") (pinfunction "1_1") (pintype "passive"))
      (node (ref "U1-C5") (pin "1") (pinfunction "1_1") (pintype "passive"))
      (node (ref "V0-C4") (pin "1") (pinfunction "1_1") (pintype "passive"))
      (node (ref "V0-C5") (pin "1") (pinfunction "1_1") (pintype "passive"))
      (node (ref "V1-C4") (pin "1") (pinfunction "1_1") (pintype "passive"))
      (node (ref "V1-C5") (pin "1") (pinfunction "1_1") (pintype "passive"))
      (node (ref "W0-C4") (pin "1") (pinfunction "1_1") (pintype "passive"))
      (node (ref "W0-C5") (pin "1") (pinfunction "1_1") (pintype "passive"))
      (node (ref "W1-C4") (pin "1") (pinfunction "1_1") (pintype "passive"))
      (node (ref "W1-C5") (pin "1") (pinfunction "1_1") (pintype "passive"))
    )
    (net (code "72") (name "W0") (class "Default")
      (node (ref "HB-W0") (pin "4") (pinfunction "OUT_4") (pintype "power_in"))
      (node (ref "HB-W0") (pin "8") (pinfunction "OUT_8") (pintype "power_in"))
      (node (ref "MOTOR0") (pin "3") (pinfunction "3_3") (pintype "passive"))
      (node (ref "W0-C3") (pin "2") (pinfunction "2_2") (pintype "passive"))
      (node (ref "W0-C5") (pin "2") (pinfunction "2_2") (pintype "passive"))
    )
    (net (code "73") (name "W1") (class "Default")
      (node (ref "HB-W1") (pin "4") (pinfunction "OUT_4") (pintype "power_in"))
      (node (ref "HB-W1") (pin "8") (pinfunction "OUT_8") (pintype "power_in"))
      (node (ref "MOTOR1") (pin "3") (pinfunction "3_3") (pintype "passive"))
      (node (ref "W1-C3") (pin "2") (pinfunction "2_2") (pintype "passive"))
      (node (ref "W1-C5") (pin "2") (pinfunction "2_2") (pintype "passive"))
    )
    (net (code "74") (name "unconnected-(HALL0-Pad5)") (class "Default")
      (node (ref "HALL0") (pin "5") (pinfunction "5_5") (pintype "passive"))
    )
    (net (code "75") (name "unconnected-(HALL1-Pad5)") (class "Default")
      (node (ref "HALL1") (pin "5") (pinfunction "5_5") (pintype "passive"))
    )
    (net (code "76") (name "unconnected-(IC0-4{slash}CAN-RX{slash}PWM-Pad4)") (class "Default")
      (node (ref "IC0") (pin "4") (pinfunction "4/CAN-RX/PWM_4") (pintype "bidirectional"))
    )
    (net (code "77") (name "unconnected-(IC0-7{slash}RX3-Pad7)") (class "Default")
      (node (ref "IC0") (pin "7") (pinfunction "7/RX3_7") (pintype "bidirectional"))
    )
    (net (code "78") (name "unconnected-(IC0-8{slash}TX3-Pad8)") (class "Default")
      (node (ref "IC0") (pin "8") (pinfunction "8/TX3_8") (pintype "bidirectional"))
    )
    (net (code "79") (name "unconnected-(IC0-A14{slash}DAC-PadRESET{slash}DAC)") (class "Default")
      (node (ref "IC0") (pin "RESET/DAC") (pinfunction "A14/DAC_RESET/DAC") (pintype "bidirectional"))
    )
    (net (code "80") (name "unconnected-(IC0-PadPGM)") (class "Default")
      (node (ref "IC0") (pin "PGM") (pinfunction "PGM_PGM") (pintype "bidirectional"))
    )
  )
)
